# CON_MEZZANINE_ANALOG.net
KiCad netlist of a schematic drawn in Altium Designer
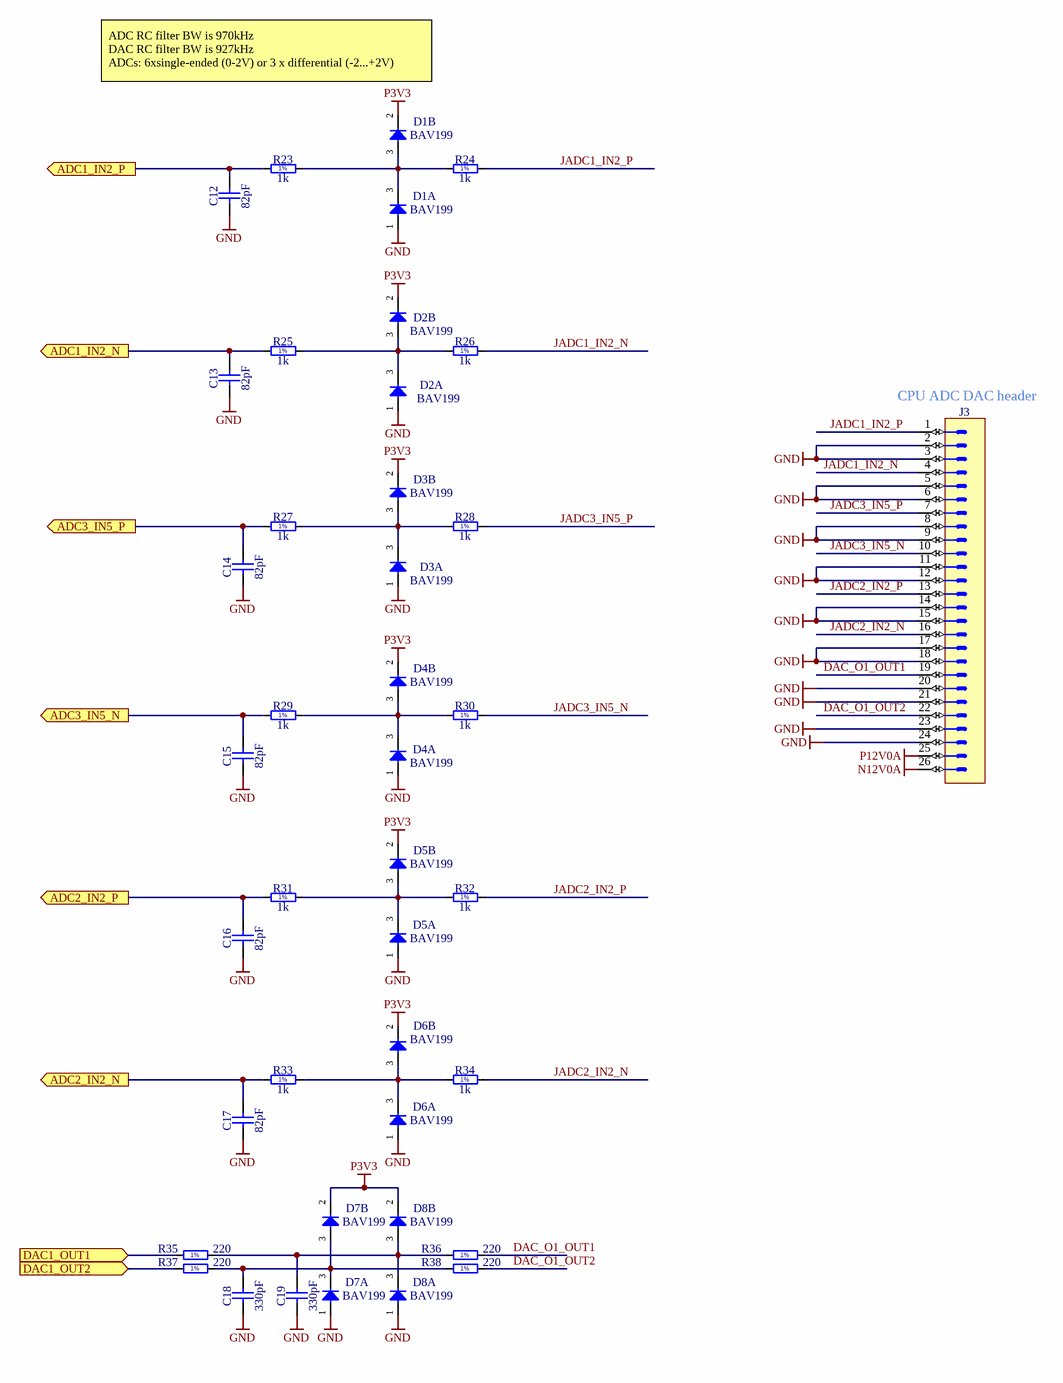
[diagram p0: CON_MEZZANINE_ANALOG.SchDoc]

(export (version "E")
  (design (tool "Eeschema 10.0.6"))
  (components
    (comp (ref "C12")
      (value "82pF")
      (footprint "CAPC1608X87N")
      (description "Non-polarised capacitor")
      (fields
        (field (name "PART NUMBER") "CC0603_82PF_50V_5%_NP0")
        (field (name "VOLTAGE") "50V")
        (field (name "AUTHOR") "CERN DEM JLC")
      )
      (libsource (lib "Capacitors") (part "Capacitor - non polarized"))
    )
    (comp (ref "C13")
      (value "82pF")
      (footprint "CAPC1608X87N")
      (description "Non-polarised capacitor")
      (fields
        (field (name "PART NUMBER") "CC0603_82PF_50V_5%_NP0")
        (field (name "VOLTAGE") "50V")
        (field (name "AUTHOR") "CERN DEM JLC")
      )
      (libsource (lib "Capacitors") (part "Capacitor - non polarized"))
    )
    (comp (ref "C14")
      (value "82pF")
      (footprint "CAPC1608X87N")
      (description "Non-polarised capacitor")
      (fields
        (field (name "PART NUMBER") "CC0603_82PF_50V_5%_NP0")
        (field (name "VOLTAGE") "50V")
        (field (name "AUTHOR") "CERN DEM JLC")
      )
      (libsource (lib "Capacitors") (part "Capacitor - non polarized"))
    )
    (comp (ref "C15")
      (value "82pF")
      (footprint "CAPC1608X87N")
      (description "Non-polarised capacitor")
      (fields
        (field (name "PART NUMBER") "CC0603_82PF_50V_5%_NP0")
        (field (name "VOLTAGE") "50V")
        (field (name "AUTHOR") "CERN DEM JLC")
      )
      (libsource (lib "Capacitors") (part "Capacitor - non polarized"))
    )
    (comp (ref "C16")
      (value "82pF")
      (footprint "CAPC1608X87N")
      (description "Non-polarised capacitor")
      (fields
        (field (name "PART NUMBER") "CC0603_82PF_50V_5%_NP0")
        (field (name "VOLTAGE") "50V")
        (field (name "AUTHOR") "CERN DEM JLC")
      )
      (libsource (lib "Capacitors") (part "Capacitor - non polarized"))
    )
    (comp (ref "C17")
      (value "82pF")
      (footprint "CAPC1608X87N")
      (description "Non-polarised capacitor")
      (fields
        (field (name "PART NUMBER") "CC0603_82PF_50V_5%_NP0")
        (field (name "VOLTAGE") "50V")
        (field (name "AUTHOR") "CERN DEM JLC")
      )
      (libsource (lib "Capacitors") (part "Capacitor - non polarized"))
    )
    (comp (ref "C18")
      (value "330pF")
      (footprint "CAPC1608X87N")
      (description "Non-polarised capacitor")
      (fields
        (field (name "PART NUMBER") "CC0603_330PF_50V_1%_NP0")
        (field (name "VOLTAGE") "50V")
        (field (name "AUTHOR") "CERN DEM MR")
      )
      (libsource (lib "Capacitors") (part "Capacitor - non polarized"))
    )
    (comp (ref "C19")
      (value "330pF")
      (footprint "CAPC1608X87N")
      (description "Non-polarised capacitor")
      (fields
        (field (name "PART NUMBER") "CC0603_330PF_50V_1%_NP0")
        (field (name "VOLTAGE") "50V")
        (field (name "AUTHOR") "CERN DEM MR")
      )
      (libsource (lib "Capacitors") (part "Capacitor - non polarized"))
    )
    (comp (ref "D1")
      (value "BAV199")
      (footprint "SOT95P240X110-3N")
      (description "Serial Diode")
      (fields
        (field (name "VOLTAGE") "75V")
        (field (name "POWER") "250mW")
        (field (name "AUTHOR") "CERN DEM JMW")
      )
      (libsource (lib "ICs And Semiconductors") (part "Diode x2 A1C3_A3C2"))
    )
    (comp (ref "D2")
      (value "BAV199")
      (footprint "SOT95P240X110-3N")
      (description "Serial Diode")
      (fields
        (field (name "VOLTAGE") "75V")
        (field (name "POWER") "250mW")
        (field (name "AUTHOR") "CERN DEM JMW")
      )
      (libsource (lib "ICs And Semiconductors") (part "Diode x2 A1C3_A3C2"))
    )
    (comp (ref "D3")
      (value "BAV199")
      (footprint "SOT95P240X110-3N")
      (description "Serial Diode")
      (fields
        (field (name "VOLTAGE") "75V")
        (field (name "POWER") "250mW")
        (field (name "AUTHOR") "CERN DEM JMW")
      )
      (libsource (lib "ICs And Semiconductors") (part "Diode x2 A1C3_A3C2"))
    )
    (comp (ref "D4")
      (value "BAV199")
      (footprint "SOT95P240X110-3N")
      (description "Serial Diode")
      (fields
        (field (name "VOLTAGE") "75V")
        (field (name "POWER") "250mW")
        (field (name "AUTHOR") "CERN DEM JMW")
      )
      (libsource (lib "ICs And Semiconductors") (part "Diode x2 A1C3_A3C2"))
    )
    (comp (ref "D5")
      (value "BAV199")
      (footprint "SOT95P240X110-3N")
      (description "Serial Diode")
      (fields
        (field (name "VOLTAGE") "75V")
        (field (name "POWER") "250mW")
        (field (name "AUTHOR") "CERN DEM JMW")
      )
      (libsource (lib "ICs And Semiconductors") (part "Diode x2 A1C3_A3C2"))
    )
    (comp (ref "D6")
      (value "BAV199")
      (footprint "SOT95P240X110-3N")
      (description "Serial Diode")
      (fields
        (field (name "VOLTAGE") "75V")
        (field (name "POWER") "250mW")
        (field (name "AUTHOR") "CERN DEM JMW")
      )
      (libsource (lib "ICs And Semiconductors") (part "Diode x2 A1C3_A3C2"))
    )
    (comp (ref "D7")
      (value "BAV199")
      (footprint "SOT95P240X110-3N")
      (description "Serial Diode")
      (fields
        (field (name "VOLTAGE") "75V")
        (field (name "POWER") "250mW")
        (field (name "AUTHOR") "CERN DEM JMW")
      )
      (libsource (lib "ICs And Semiconductors") (part "Diode x2 A1C3_A3C2"))
    )
    (comp (ref "D8")
      (value "BAV199")
      (footprint "SOT95P240X110-3N")
      (description "Serial Diode")
      (fields
        (field (name "VOLTAGE") "75V")
        (field (name "POWER") "250mW")
        (field (name "AUTHOR") "CERN DEM JMW")
      )
      (libsource (lib "ICs And Semiconductors") (part "Diode x2 A1C3_A3C2"))
    )
    (comp (ref "J3")
      (value "Header 26")
      (footprint "3M_N2526-6002RB")
      (description "Connector 26 Male")
      (fields
        (field (name "PART NUMBER") "3M_N2526-6002RB")
        (field (name "MANUFACTURER") "3M")
        (field (name "AUTHOR") "CERN DEM JLC")
      )
      (libsource (lib "Connectors") (part "Connector 26 Male"))
    )
    (comp (ref "R23")
      (value "1k")
      (footprint "RESC1005X40N")
      (description "Resistor - 1%")
      (fields
        (field (name "PART NUMBER") "R0402_1K_1%_0.0625W_100PPM")
        (field (name "POWER") "0.0625W")
        (field (name "AUTHOR") "CERN DEM JLC")
      )
      (libsource (lib "Resistors") (part "Resistor - 1%"))
    )
    (comp (ref "R24")
      (value "1k")
      (footprint "RESC1005X40N")
      (description "Resistor - 1%")
      (fields
        (field (name "PART NUMBER") "R0402_1K_1%_0.0625W_100PPM")
        (field (name "POWER") "0.0625W")
        (field (name "AUTHOR") "CERN DEM JLC")
      )
      (libsource (lib "Resistors") (part "Resistor - 1%"))
    )
    (comp (ref "R25")
      (value "1k")
      (footprint "RESC1005X40N")
      (description "Resistor - 1%")
      (fields
        (field (name "PART NUMBER") "R0402_1K_1%_0.0625W_100PPM")
        (field (name "POWER") "0.0625W")
        (field (name "AUTHOR") "CERN DEM JLC")
      )
      (libsource (lib "Resistors") (part "Resistor - 1%"))
    )
    (comp (ref "R26")
      (value "1k")
      (footprint "RESC1005X40N")
      (description "Resistor - 1%")
      (fields
        (field (name "PART NUMBER") "R0402_1K_1%_0.0625W_100PPM")
        (field (name "POWER") "0.0625W")
        (field (name "AUTHOR") "CERN DEM JLC")
      )
      (libsource (lib "Resistors") (part "Resistor - 1%"))
    )
    (comp (ref "R27")
      (value "1k")
      (footprint "RESC1005X40N")
      (description "Resistor - 1%")
      (fields
        (field (name "PART NUMBER") "R0402_1K_1%_0.0625W_100PPM")
        (field (name "POWER") "0.0625W")
        (field (name "AUTHOR") "CERN DEM JLC")
      )
      (libsource (lib "Resistors") (part "Resistor - 1%"))
    )
    (comp (ref "R28")
      (value "1k")
      (footprint "RESC1005X40N")
      (description "Resistor - 1%")
      (fields
        (field (name "PART NUMBER") "R0402_1K_1%_0.0625W_100PPM")
        (field (name "POWER") "0.0625W")
        (field (name "AUTHOR") "CERN DEM JLC")
      )
      (libsource (lib "Resistors") (part "Resistor - 1%"))
    )
    (comp (ref "R29")
      (value "1k")
      (footprint "RESC1005X40N")
      (description "Resistor - 1%")
      (fields
        (field (name "PART NUMBER") "R0402_1K_1%_0.0625W_100PPM")
        (field (name "POWER") "0.0625W")
        (field (name "AUTHOR") "CERN DEM JLC")
      )
      (libsource (lib "Resistors") (part "Resistor - 1%"))
    )
    (comp (ref "R30")
      (value "1k")
      (footprint "RESC1005X40N")
      (description "Resistor - 1%")
      (fields
        (field (name "PART NUMBER") "R0402_1K_1%_0.0625W_100PPM")
        (field (name "POWER") "0.0625W")
        (field (name "AUTHOR") "CERN DEM JLC")
      )
      (libsource (lib "Resistors") (part "Resistor - 1%"))
    )
    (comp (ref "R31")
      (value "1k")
      (footprint "RESC1005X40N")
      (description "Resistor - 1%")
      (fields
        (field (name "PART NUMBER") "R0402_1K_1%_0.0625W_100PPM")
        (field (name "POWER") "0.0625W")
        (field (name "AUTHOR") "CERN DEM JLC")
      )
      (libsource (lib "Resistors") (part "Resistor - 1%"))
    )
    (comp (ref "R32")
      (value "1k")
      (footprint "RESC1005X40N")
      (description "Resistor - 1%")
      (fields
        (field (name "PART NUMBER") "R0402_1K_1%_0.0625W_100PPM")
        (field (name "POWER") "0.0625W")
        (field (name "AUTHOR") "CERN DEM JLC")
      )
      (libsource (lib "Resistors") (part "Resistor - 1%"))
    )
    (comp (ref "R33")
      (value "1k")
      (footprint "RESC1005X40N")
      (description "Resistor - 1%")
      (fields
        (field (name "PART NUMBER") "R0402_1K_1%_0.0625W_100PPM")
        (field (name "POWER") "0.0625W")
        (field (name "AUTHOR") "CERN DEM JLC")
      )
      (libsource (lib "Resistors") (part "Resistor - 1%"))
    )
    (comp (ref "R34")
      (value "1k")
      (footprint "RESC1005X40N")
      (description "Resistor - 1%")
      (fields
        (field (name "PART NUMBER") "R0402_1K_1%_0.0625W_100PPM")
        (field (name "POWER") "0.0625W")
        (field (name "AUTHOR") "CERN DEM JLC")
      )
      (libsource (lib "Resistors") (part "Resistor - 1%"))
    )
    (comp (ref "R35")
      (value "220")
      (footprint "RESC1608X55N")
      (description "Resistor - 1%")
      (fields
        (field (name "PART NUMBER") "R0603_220R_1%_0.1W_100PPM")
        (field (name "POWER") "0.1W")
        (field (name "AUTHOR") "CERN DEM JLC")
      )
      (libsource (lib "Resistors") (part "Resistor - 1%"))
    )
    (comp (ref "R36")
      (value "220")
      (footprint "RESC1608X55N")
      (description "Resistor - 1%")
      (fields
        (field (name "PART NUMBER") "R0603_220R_1%_0.1W_100PPM")
        (field (name "POWER") "0.1W")
        (field (name "AUTHOR") "CERN DEM JLC")
      )
      (libsource (lib "Resistors") (part "Resistor - 1%"))
    )
    (comp (ref "R37")
      (value "220")
      (footprint "RESC1608X55N")
      (description "Resistor - 1%")
      (fields
        (field (name "PART NUMBER") "R0603_220R_1%_0.1W_100PPM")
        (field (name "POWER") "0.1W")
        (field (name "AUTHOR") "CERN DEM JLC")
      )
      (libsource (lib "Resistors") (part "Resistor - 1%"))
    )
    (comp (ref "R38")
      (value "220")
      (footprint "RESC1608X55N")
      (description "Resistor - 1%")
      (fields
        (field (name "PART NUMBER") "R0603_220R_1%_0.1W_100PPM")
        (field (name "POWER") "0.1W")
        (field (name "AUTHOR") "CERN DEM JLC")
      )
      (libsource (lib "Resistors") (part "Resistor - 1%"))
    )
  )
  (nets
    (net (code "1") (name "/ADC1_IN2_N") (class "Default")
      (node (ref "C13") (pin "2") (pinfunction "2_2") (pintype "passive"))
      (node (ref "R25") (pin "1") (pinfunction "1_1") (pintype "passive"))
    )
    (net (code "2") (name "/ADC1_IN2_P") (class "Default")
      (node (ref "C12") (pin "2") (pinfunction "2_2") (pintype "passive"))
      (node (ref "R23") (pin "1") (pinfunction "1_1") (pintype "passive"))
    )
    (net (code "3") (name "/ADC2_IN2_N") (class "Default")
      (node (ref "C17") (pin "2") (pinfunction "2_2") (pintype "passive"))
      (node (ref "R33") (pin "1") (pinfunction "1_1") (pintype "passive"))
    )
    (net (code "4") (name "/ADC2_IN2_P") (class "Default")
      (node (ref "C16") (pin "2") (pinfunction "2_2") (pintype "passive"))
      (node (ref "R31") (pin "1") (pinfunction "1_1") (pintype "passive"))
    )
    (net (code "5") (name "/ADC3_IN5_N") (class "Default")
      (node (ref "C15") (pin "2") (pinfunction "2_2") (pintype "passive"))
      (node (ref "R29") (pin "1") (pinfunction "1_1") (pintype "passive"))
    )
    (net (code "6") (name "/ADC3_IN5_P") (class "Default")
      (node (ref "C14") (pin "2") (pinfunction "2_2") (pintype "passive"))
      (node (ref "R27") (pin "1") (pinfunction "1_1") (pintype "passive"))
    )
    (net (code "7") (name "/DAC1_OUT1") (class "Default")
      (node (ref "R35") (pin "1") (pinfunction "1_1") (pintype "passive"))
    )
    (net (code "8") (name "/DAC1_OUT2") (class "Default")
      (node (ref "R37") (pin "1") (pinfunction "1_1") (pintype "passive"))
    )
    (net (code "9") (name "/DAC_O1_OUT1") (class "Default")
      (node (ref "J3") (pin "19") (pinfunction "19_19") (pintype "bidirectional"))
      (node (ref "R36") (pin "2") (pinfunction "2_2") (pintype "passive"))
    )
    (net (code "10") (name "/DAC_O1_OUT2") (class "Default")
      (node (ref "J3") (pin "22") (pinfunction "22_22") (pintype "bidirectional"))
      (node (ref "R38") (pin "2") (pinfunction "2_2") (pintype "passive"))
    )
    (net (code "11") (name "/JADC1_IN2_N") (class "Default")
      (node (ref "J3") (pin "4") (pinfunction "4_4") (pintype "bidirectional"))
      (node (ref "R26") (pin "2") (pinfunction "2_2") (pintype "passive"))
    )
    (net (code "12") (name "/JADC1_IN2_P") (class "Default")
      (node (ref "J3") (pin "1") (pinfunction "1_1") (pintype "bidirectional"))
      (node (ref "R24") (pin "2") (pinfunction "2_2") (pintype "passive"))
    )
    (net (code "13") (name "/JADC2_IN2_N") (class "Default")
      (node (ref "J3") (pin "16") (pinfunction "16_16") (pintype "bidirectional"))
      (node (ref "R34") (pin "2") (pinfunction "2_2") (pintype "passive"))
    )
    (net (code "14") (name "/JADC2_IN2_P") (class "Default")
      (node (ref "J3") (pin "13") (pinfunction "13_13") (pintype "bidirectional"))
      (node (ref "R32") (pin "2") (pinfunction "2_2") (pintype "passive"))
    )
    (net (code "15") (name "/JADC3_IN5_N") (class "Default")
      (node (ref "J3") (pin "10") (pinfunction "10_10") (pintype "bidirectional"))
      (node (ref "R30") (pin "2") (pinfunction "2_2") (pintype "passive"))
    )
    (net (code "16") (name "/JADC3_IN5_P") (class "Default")
      (node (ref "J3") (pin "7") (pinfunction "7_7") (pintype "bidirectional"))
      (node (ref "R28") (pin "2") (pinfunction "2_2") (pintype "passive"))
    )
    (net (code "17") (name "GND") (class "Default")
      (node (ref "C12") (pin "1") (pinfunction "1_1") (pintype "passive"))
      (node (ref "C13") (pin "1") (pinfunction "1_1") (pintype "passive"))
      (node (ref "C14") (pin "1") (pinfunction "1_1") (pintype "passive"))
      (node (ref "C15") (pin "1") (pinfunction "1_1") (pintype "passive"))
      (node (ref "C16") (pin "1") (pinfunction "1_1") (pintype "passive"))
      (node (ref "C17") (pin "1") (pinfunction "1_1") (pintype "passive"))
      (node (ref "C18") (pin "1") (pinfunction "1_1") (pintype "passive"))
      (node (ref "C19") (pin "1") (pinfunction "1_1") (pintype "passive"))
      (node (ref "D1") (pin "1") (pinfunction "A_1") (pintype "passive"))
      (node (ref "D2") (pin "1") (pinfunction "A_1") (pintype "passive"))
      (node (ref "D3") (pin "1") (pinfunction "A_1") (pintype "passive"))
      (node (ref "D4") (pin "1") (pinfunction "A_1") (pintype "passive"))
      (node (ref "D5") (pin "1") (pinfunction "A_1") (pintype "passive"))
      (node (ref "D6") (pin "1") (pinfunction "A_1") (pintype "passive"))
      (node (ref "D7") (pin "1") (pinfunction "A_1") (pintype "passive"))
      (node (ref "D8") (pin "1") (pinfunction "A_1") (pintype "passive"))
      (node (ref "J3") (pin "11") (pinfunction "11_11") (pintype "bidirectional"))
      (node (ref "J3") (pin "12") (pinfunction "12_12") (pintype "bidirectional"))
      (node (ref "J3") (pin "14") (pinfunction "14_14") (pintype "bidirectional"))
      (node (ref "J3") (pin "15") (pinfunction "15_15") (pintype "bidirectional"))
      (node (ref "J3") (pin "17") (pinfunction "17_17") (pintype "bidirectional"))
      (node (ref "J3") (pin "18") (pinfunction "18_18") (pintype "bidirectional"))
      (node (ref "J3") (pin "2") (pinfunction "2_2") (pintype "bidirectional"))
      (node (ref "J3") (pin "20") (pinfunction "20_20") (pintype "bidirectional"))
      (node (ref "J3") (pin "21") (pinfunction "21_21") (pintype "bidirectional"))
      (node (ref "J3") (pin "23") (pinfunction "23_23") (pintype "bidirectional"))
      (node (ref "J3") (pin "24") (pinfunction "24_24") (pintype "bidirectional"))
      (node (ref "J3") (pin "3") (pinfunction "3_3") (pintype "bidirectional"))
      (node (ref "J3") (pin "5") (pinfunction "5_5") (pintype "bidirectional"))
      (node (ref "J3") (pin "6") (pinfunction "6_6") (pintype "bidirectional"))
      (node (ref "J3") (pin "8") (pinfunction "8_8") (pintype "bidirectional"))
      (node (ref "J3") (pin "9") (pinfunction "9_9") (pintype "bidirectional"))
    )
    (net (code "18") (name "N12V0A") (class "Default")
      (node (ref "J3") (pin "26") (pinfunction "26_26") (pintype "bidirectional"))
    )
    (net (code "19") (name "Net-(D1A-COMAC)") (class "Default")
      (node (ref "D1") (pin "3") (pinfunction "COMAC_3") (pintype "passive"))
      (node (ref "R23") (pin "2") (pinfunction "2_2") (pintype "passive"))
      (node (ref "R24") (pin "1") (pinfunction "1_1") (pintype "passive"))
    )
    (net (code "20") (name "Net-(D2A-COMAC)") (class "Default")
      (node (ref "D2") (pin "3") (pinfunction "COMAC_3") (pintype "passive"))
      (node (ref "R25") (pin "2") (pinfunction "2_2") (pintype "passive"))
      (node (ref "R26") (pin "1") (pinfunction "1_1") (pintype "passive"))
    )
    (net (code "21") (name "Net-(D3A-COMAC)") (class "Default")
      (node (ref "D3") (pin "3") (pinfunction "COMAC_3") (pintype "passive"))
      (node (ref "R27") (pin "2") (pinfunction "2_2") (pintype "passive"))
      (node (ref "R28") (pin "1") (pinfunction "1_1") (pintype "passive"))
    )
    (net (code "22") (name "Net-(D4A-COMAC)") (class "Default")
      (node (ref "D4") (pin "3") (pinfunction "COMAC_3") (pintype "passive"))
      (node (ref "R29") (pin "2") (pinfunction "2_2") (pintype "passive"))
      (node (ref "R30") (pin "1") (pinfunction "1_1") (pintype "passive"))
    )
    (net (code "23") (name "Net-(D5A-COMAC)") (class "Default")
      (node (ref "D5") (pin "3") (pinfunction "COMAC_3") (pintype "passive"))
      (node (ref "R31") (pin "2") (pinfunction "2_2") (pintype "passive"))
      (node (ref "R32") (pin "1") (pinfunction "1_1") (pintype "passive"))
    )
    (net (code "24") (name "Net-(D6A-COMAC)") (class "Default")
      (node (ref "D6") (pin "3") (pinfunction "COMAC_3") (pintype "passive"))
      (node (ref "R33") (pin "2") (pinfunction "2_2") (pintype "passive"))
      (node (ref "R34") (pin "1") (pinfunction "1_1") (pintype "passive"))
    )
    (net (code "25") (name "Net-(D7A-COMAC)") (class "Default")
      (node (ref "C18") (pin "2") (pinfunction "2_2") (pintype "passive"))
      (node (ref "D7") (pin "3") (pinfunction "COMAC_3") (pintype "passive"))
      (node (ref "R37") (pin "2") (pinfunction "2_2") (pintype "passive"))
      (node (ref "R38") (pin "1") (pinfunction "1_1") (pintype "passive"))
    )
    (net (code "26") (name "Net-(D8A-COMAC)") (class "Default")
      (node (ref "C19") (pin "2") (pinfunction "2_2") (pintype "passive"))
      (node (ref "D8") (pin "3") (pinfunction "COMAC_3") (pintype "passive"))
      (node (ref "R35") (pin "2") (pinfunction "2_2") (pintype "passive"))
      (node (ref "R36") (pin "1") (pinfunction "1_1") (pintype "passive"))
    )
    (net (code "27") (name "P3V3") (class "Default")
      (node (ref "D1") (pin "2") (pinfunction "C_2") (pintype "passive"))
      (node (ref "D2") (pin "2") (pinfunction "C_2") (pintype "passive"))
      (node (ref "D3") (pin "2") (pinfunction "C_2") (pintype "passive"))
      (node (ref "D4") (pin "2") (pinfunction "C_2") (pintype "passive"))
      (node (ref "D5") (pin "2") (pinfunction "C_2") (pintype "passive"))
      (node (ref "D6") (pin "2") (pinfunction "C_2") (pintype "passive"))
      (node (ref "D7") (pin "2") (pinfunction "C_2") (pintype "passive"))
      (node (ref "D8") (pin "2") (pinfunction "C_2") (pintype "passive"))
    )
    (net (code "28") (name "P12V0A") (class "Default")
      (node (ref "J3") (pin "25") (pinfunction "25_25") (pintype "bidirectional"))
    )
  )
)
